# Cosmic_Pi_Analogue_V2_5_OHL_no_logo.net
KiCad netlist of a schematic drawn in EAGLE
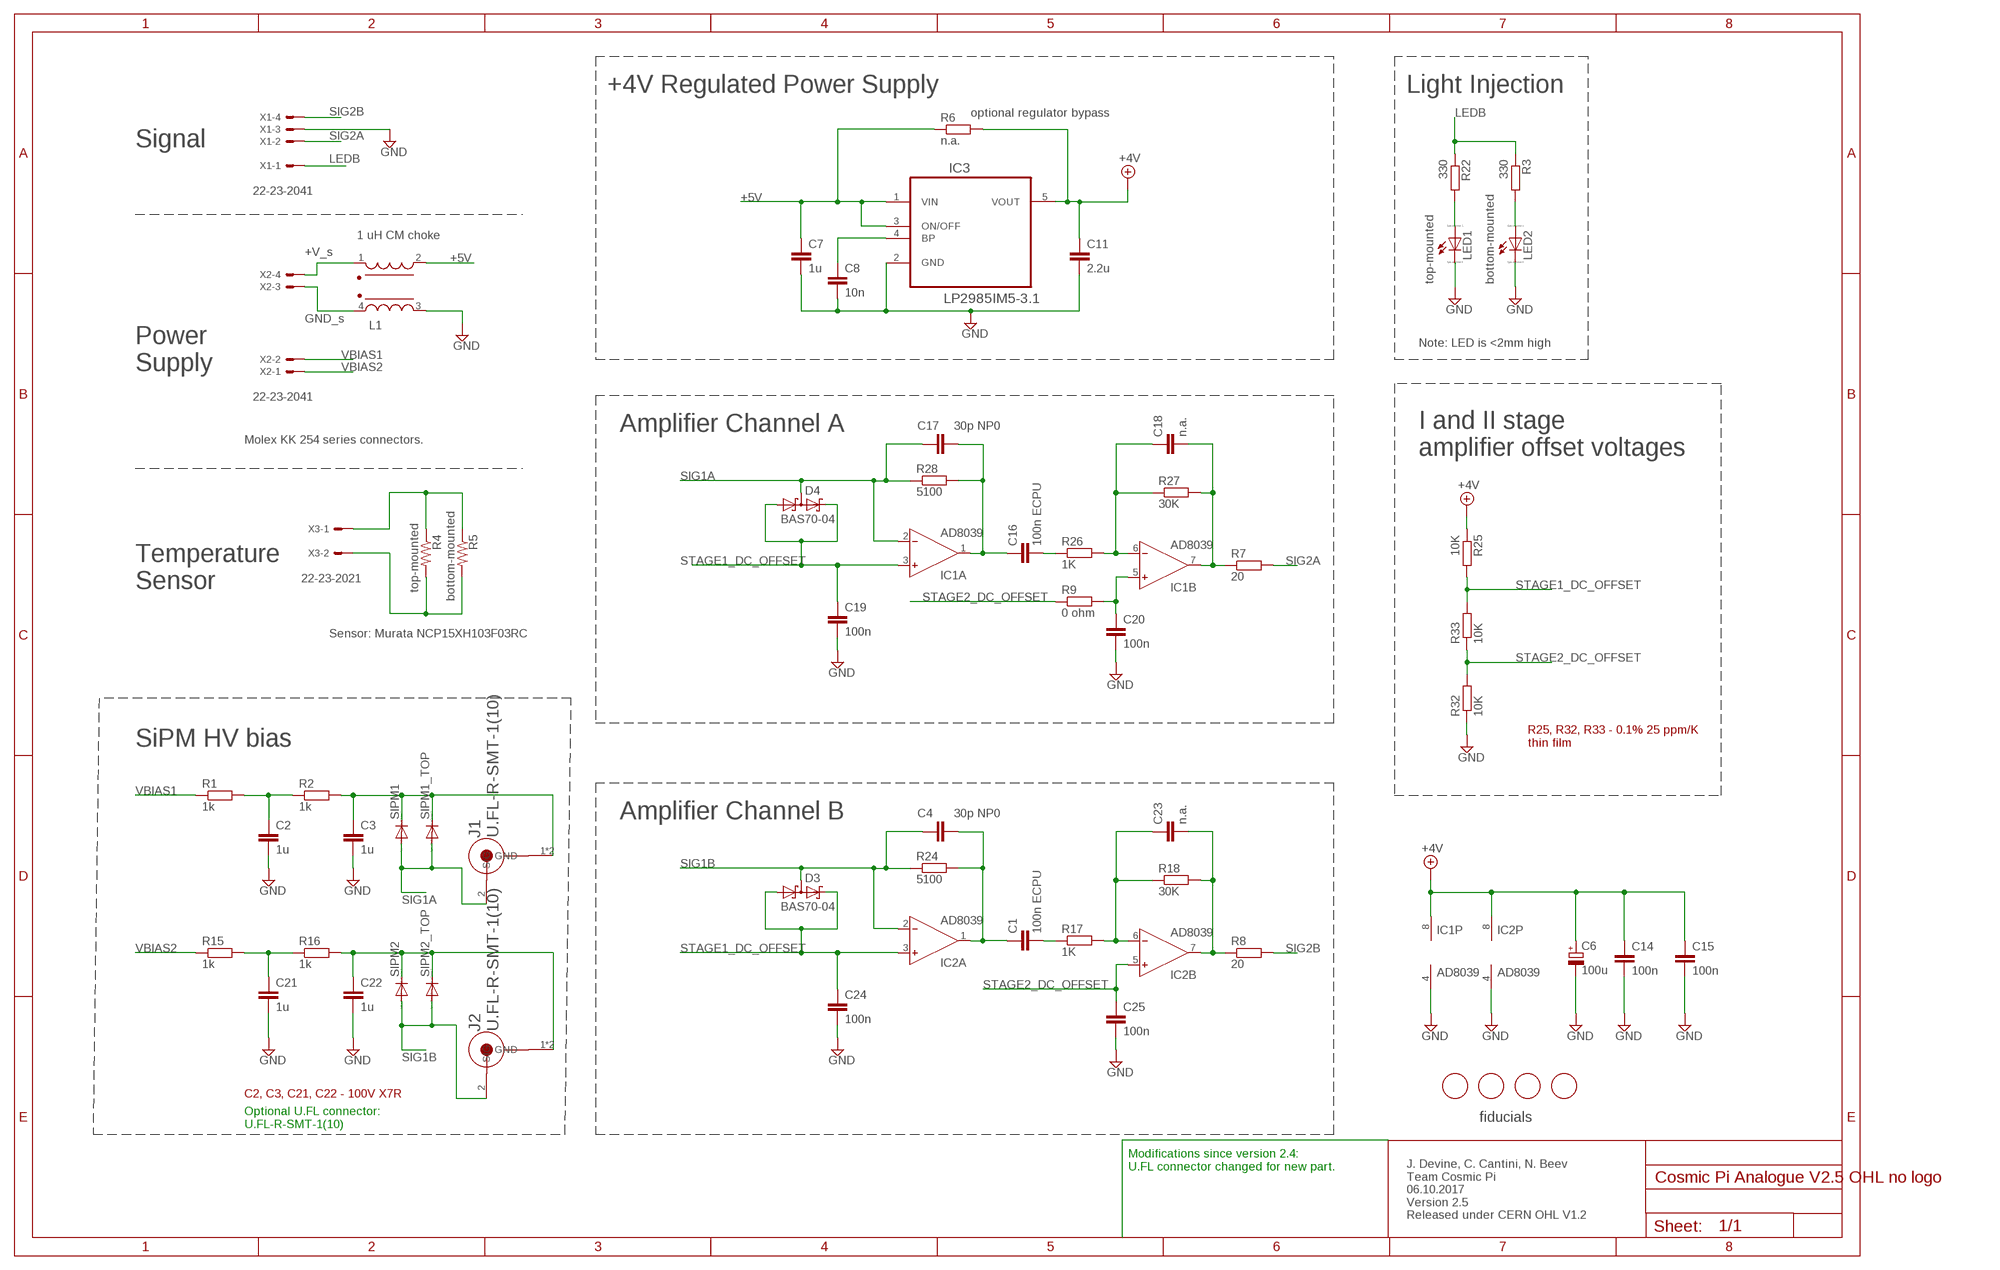
[diagram p0: schematic, sheet 1]

(export (version "E")
  (design (tool "Eeschema 10.0.6"))
  (components
    (comp (ref "C1")
      (value "100n ECPU")
      (footprint "eagle-import:C0805")
      (libsource (lib "eagle-import") (part "C-EUC0805"))
    )
    (comp (ref "C2")
      (value "1u")
      (footprint "eagle-import:C1206")
      (libsource (lib "eagle-import") (part "C-EUC1206"))
    )
    (comp (ref "C3")
      (value "1u")
      (footprint "eagle-import:C1206")
      (libsource (lib "eagle-import") (part "C-EUC1206"))
    )
    (comp (ref "C4")
      (value "30p NP0")
      (footprint "eagle-import:C0603")
      (libsource (lib "eagle-import") (part "C-EUC0603"))
    )
    (comp (ref "C6")
      (value "100u")
      (footprint "eagle-import:C_6032-28R")
      (libsource (lib "eagle-import") (part "CPOL-EUC/6032-28R"))
    )
    (comp (ref "C7")
      (value "1u")
      (footprint "eagle-import:C0603")
      (libsource (lib "eagle-import") (part "resistor_C-EUC0603"))
    )
    (comp (ref "C8")
      (value "10n")
      (footprint "eagle-import:C0603")
      (libsource (lib "eagle-import") (part "resistor_C-EUC0603"))
    )
    (comp (ref "C11")
      (value "2.2u")
      (footprint "eagle-import:C0603")
      (libsource (lib "eagle-import") (part "resistor_C-EUC0603"))
    )
    (comp (ref "C14")
      (value "100n")
      (footprint "eagle-import:C0603")
      (libsource (lib "eagle-import") (part "resistor_C-EUC0603"))
    )
    (comp (ref "C15")
      (value "100n")
      (footprint "eagle-import:C0603")
      (libsource (lib "eagle-import") (part "resistor_C-EUC0603"))
    )
    (comp (ref "C16")
      (value "100n ECPU")
      (footprint "eagle-import:C0805")
      (libsource (lib "eagle-import") (part "C-EUC0805"))
    )
    (comp (ref "C17")
      (value "30p NP0")
      (footprint "eagle-import:C0603")
      (libsource (lib "eagle-import") (part "C-EUC0603"))
    )
    (comp (ref "C18")
      (value "n.a.")
      (footprint "eagle-import:C0603")
      (libsource (lib "eagle-import") (part "C-EUC0603"))
    )
    (comp (ref "C19")
      (value "100n")
      (footprint "eagle-import:C0603")
      (libsource (lib "eagle-import") (part "resistor_C-EUC0603"))
    )
    (comp (ref "C20")
      (value "100n")
      (footprint "eagle-import:C0603")
      (libsource (lib "eagle-import") (part "resistor_C-EUC0603"))
    )
    (comp (ref "C21")
      (value "1u")
      (footprint "eagle-import:C1206")
      (libsource (lib "eagle-import") (part "C-EUC1206"))
    )
    (comp (ref "C22")
      (value "1u")
      (footprint "eagle-import:C1206")
      (libsource (lib "eagle-import") (part "C-EUC1206"))
    )
    (comp (ref "C23")
      (value "n.a.")
      (footprint "eagle-import:C0603")
      (libsource (lib "eagle-import") (part "C-EUC0603"))
    )
    (comp (ref "C24")
      (value "100n")
      (footprint "eagle-import:C0603")
      (libsource (lib "eagle-import") (part "resistor_C-EUC0603"))
    )
    (comp (ref "C25")
      (value "100n")
      (footprint "eagle-import:C0603")
      (libsource (lib "eagle-import") (part "resistor_C-EUC0603"))
    )
    (comp (ref "D3")
      (value "BAS70-04")
      (footprint "eagle-import:SOT23")
      (libsource (lib "eagle-import") (part "BAS70-04"))
    )
    (comp (ref "D4")
      (value "BAS70-04")
      (footprint "eagle-import:SOT23")
      (libsource (lib "eagle-import") (part "BAS70-04"))
    )
    (comp (ref "IC1")
      (value "AD8039")
      (footprint "eagle-import:SO8")
      (fields (field (name "MF") "ALTERA CORPORATION") (field (name "MPN") "AD8033ARZ"))
      (libsource (lib "eagle-import") (part "AD8033R"))
    )
    (comp (ref "IC2")
      (value "AD8039")
      (footprint "eagle-import:SO8")
      (fields (field (name "MF") "ALTERA CORPORATION") (field (name "MPN") "AD8033ARZ"))
      (libsource (lib "eagle-import") (part "AD8033R"))
    )
    (comp (ref "IC3")
      (value "LP2985IM5-3.1")
      (footprint "eagle-import:SOT95P284X120-5N")
      (libsource (lib "eagle-import") (part "LP2985IM5-3.1"))
    )
    (comp (ref "J1")
      (value "U.FL-R-SMT-1(10)")
      (footprint "eagle-import:HRS_U.FL-R-SMT-1(10)")
      (fields (field (name "MF") "Hirose"))
      (libsource (lib "eagle-import") (part "U.FL-R-SMT-1(10)"))
    )
    (comp (ref "J2")
      (value "U.FL-R-SMT-1(10)")
      (footprint "eagle-import:HRS_U.FL-R-SMT-1(10)")
      (fields (field (name "MF") "Hirose"))
      (libsource (lib "eagle-import") (part "U.FL-R-SMT-1(10)"))
    )
    (comp (ref "L1")
      (value "1 uH CM choke")
      (footprint "eagle-import:WE-CNSW_1812")
      (libsource (lib "eagle-import") (part "WE-CNSW_1812_744235601"))
    )
    (comp (ref "LED1")
      (value "top-mounted")
      (footprint "eagle-import:LED_SML0603")
      (libsource (lib "eagle-import") (part "LED_ESML0603"))
    )
    (comp (ref "LED2")
      (value "bottom-mounted")
      (footprint "eagle-import:LED_SML0603")
      (libsource (lib "eagle-import") (part "LED_ESML0603"))
    )
    (comp (ref "R1")
      (value "1k")
      (footprint "eagle-import:R1206")
      (libsource (lib "eagle-import") (part "R-EU_R1206"))
    )
    (comp (ref "R2")
      (value "1k")
      (footprint "eagle-import:R1206")
      (libsource (lib "eagle-import") (part "R-EU_R1206"))
    )
    (comp (ref "R3")
      (value "330")
      (footprint "eagle-import:R0603")
      (libsource (lib "eagle-import") (part "resistor_R-EU_R0603"))
    )
    (comp (ref "R4")
      (value "top-mounted")
      (footprint "eagle-import:R0402")
      (libsource (lib "eagle-import") (part "R-US_R0402"))
    )
    (comp (ref "R5")
      (value "bottom-mounted")
      (footprint "eagle-import:R0402")
      (libsource (lib "eagle-import") (part "R-US_R0402"))
    )
    (comp (ref "R6")
      (value "n.a.")
      (footprint "eagle-import:R0603")
      (libsource (lib "eagle-import") (part "R-EU_R0603"))
    )
    (comp (ref "R7")
      (value "20")
      (footprint "eagle-import:R0603")
      (libsource (lib "eagle-import") (part "R-EU_R0603"))
    )
    (comp (ref "R8")
      (value "20")
      (footprint "eagle-import:R0603")
      (libsource (lib "eagle-import") (part "R-EU_R0603"))
    )
    (comp (ref "R9")
      (value "0 ohm")
      (footprint "eagle-import:R1206")
      (libsource (lib "eagle-import") (part "R-EU_R1206"))
    )
    (comp (ref "R15")
      (value "1k")
      (footprint "eagle-import:R1206")
      (libsource (lib "eagle-import") (part "R-EU_R1206"))
    )
    (comp (ref "R16")
      (value "1k")
      (footprint "eagle-import:R1206")
      (libsource (lib "eagle-import") (part "R-EU_R1206"))
    )
    (comp (ref "R17")
      (value "1K")
      (footprint "eagle-import:R0603")
      (libsource (lib "eagle-import") (part "R-EU_R0603"))
    )
    (comp (ref "R18")
      (value "30K")
      (footprint "eagle-import:R0603")
      (libsource (lib "eagle-import") (part "R-EU_R0603"))
    )
    (comp (ref "R22")
      (value "330")
      (footprint "eagle-import:R0603")
      (libsource (lib "eagle-import") (part "resistor_R-EU_R0603"))
    )
    (comp (ref "R24")
      (value "5100")
      (footprint "eagle-import:R0603")
      (libsource (lib "eagle-import") (part "R-EU_R0603"))
    )
    (comp (ref "R25")
      (value "10K")
      (footprint "eagle-import:R0805")
      (libsource (lib "eagle-import") (part "R-EU_R0805"))
    )
    (comp (ref "R26")
      (value "1K")
      (footprint "eagle-import:R0603")
      (libsource (lib "eagle-import") (part "R-EU_R0603"))
    )
    (comp (ref "R27")
      (value "30K")
      (footprint "eagle-import:R0603")
      (libsource (lib "eagle-import") (part "R-EU_R0603"))
    )
    (comp (ref "R28")
      (value "5100")
      (footprint "eagle-import:R0603")
      (libsource (lib "eagle-import") (part "R-EU_R0603"))
    )
    (comp (ref "R32")
      (value "10K")
      (footprint "eagle-import:R0805")
      (libsource (lib "eagle-import") (part "R-EU_R0805"))
    )
    (comp (ref "R33")
      (value "10K")
      (footprint "eagle-import:R0805")
      (libsource (lib "eagle-import") (part "R-EU_R0805"))
    )
    (comp (ref "SIPM1")
      (value "DIODE-ADVANSID")
      (footprint "eagle-import:ASD-NUV3S-P")
      (libsource (lib "eagle-import") (part "DIODE-ADVANSID"))
    )
    (comp (ref "SIPM1_TOP")
      (value "DIODE-ADVANSID")
      (footprint "eagle-import:ASD-NUV3S-P")
      (libsource (lib "eagle-import") (part "DIODE-ADVANSID"))
    )
    (comp (ref "SIPM2")
      (value "DIODE-ADVANSID")
      (footprint "eagle-import:ASD-NUV3S-P")
      (libsource (lib "eagle-import") (part "DIODE-ADVANSID"))
    )
    (comp (ref "SIPM2_TOP")
      (value "DIODE-ADVANSID")
      (footprint "eagle-import:ASD-NUV3S-P")
      (libsource (lib "eagle-import") (part "DIODE-ADVANSID"))
    )
    (comp (ref "U$2")
      (value "FIDUCIAL")
      (footprint "eagle-import:FIDUCIAL_1MM")
      (libsource (lib "eagle-import") (part "FIDUCIAL"))
    )
    (comp (ref "U$3")
      (value "FIDUCIAL")
      (footprint "eagle-import:FIDUCIAL_1MM")
      (libsource (lib "eagle-import") (part "FIDUCIAL"))
    )
    (comp (ref "U$4")
      (value "FIDUCIAL")
      (footprint "eagle-import:FIDUCIAL_1MM")
      (libsource (lib "eagle-import") (part "FIDUCIAL"))
    )
    (comp (ref "U$5")
      (value "FIDUCIAL")
      (footprint "eagle-import:FIDUCIAL_1MM")
      (libsource (lib "eagle-import") (part "FIDUCIAL"))
    )
    (comp (ref "X1")
      (value "22-23-2041")
      (footprint "eagle-import:22-23-2041")
      (fields (field (name "MF") "MOLEX"))
      (libsource (lib "eagle-import") (part "22-23-2041"))
    )
    (comp (ref "X2")
      (value "22-23-2041")
      (footprint "eagle-import:22-23-2041")
      (fields (field (name "MF") "MOLEX"))
      (libsource (lib "eagle-import") (part "22-23-2041"))
    )
    (comp (ref "X3")
      (value "22-23-2021")
      (footprint "eagle-import:22-23-2021")
      (fields (field (name "MF") "MOLEX"))
      (libsource (lib "eagle-import") (part "22-23-2021"))
    )
  )
  (nets
    (net (code "1") (name "+4V") (class "Default")
      (node (ref "C11") (pin "1") (pinfunction "1_1") (pintype "passive"))
      (node (ref "C14") (pin "1") (pinfunction "1_1") (pintype "passive"))
      (node (ref "C15") (pin "1") (pinfunction "1_1") (pintype "passive"))
      (node (ref "C6") (pin "+") (pinfunction "+_+") (pintype "passive"))
      (node (ref "IC1") (pin "8") (pinfunction "V+_8") (pintype "power_in"))
      (node (ref "IC2") (pin "8") (pinfunction "V+_8") (pintype "power_in"))
      (node (ref "IC3") (pin "5") (pinfunction "VOUT_5") (pintype "output"))
      (node (ref "R25") (pin "1") (pinfunction "1_1") (pintype "passive"))
      (node (ref "R6") (pin "2") (pinfunction "2_2") (pintype "passive"))
    )
    (net (code "2") (name "/+5V") (class "Default")
      (node (ref "C7") (pin "1") (pinfunction "1_1") (pintype "passive"))
      (node (ref "IC3") (pin "1") (pinfunction "VIN_1") (pintype "power_in"))
      (node (ref "IC3") (pin "3") (pinfunction "ON/OFF_3") (pintype "input"))
      (node (ref "L1") (pin "2") (pinfunction "3_2") (pintype "passive"))
      (node (ref "R6") (pin "1") (pinfunction "1_1") (pintype "passive"))
    )
    (net (code "3") (name "/LEDB") (class "Default")
      (node (ref "R22") (pin "1") (pinfunction "1_1") (pintype "passive"))
      (node (ref "R3") (pin "1") (pinfunction "1_1") (pintype "passive"))
      (node (ref "X1") (pin "1") (pinfunction "S_1") (pintype "passive"))
    )
    (net (code "4") (name "/SIG1A") (class "Default")
      (node (ref "C17") (pin "1") (pinfunction "1_1") (pintype "passive"))
      (node (ref "D4") (pin "3") (pinfunction "C1A2_3") (pintype "passive"))
      (node (ref "IC1") (pin "2") (pinfunction "IN-_2") (pintype "input"))
      (node (ref "J1") (pin "2") (pinfunction "SIG_2") (pintype "passive"))
      (node (ref "R28") (pin "1") (pinfunction "1_1") (pintype "passive"))
      (node (ref "SIPM1") (pin "P$2") (pinfunction "A_P$2") (pintype "passive"))
      (node (ref "SIPM1_TOP") (pin "P$2") (pinfunction "A_P$2") (pintype "passive"))
    )
    (net (code "5") (name "/SIG1B") (class "Default")
      (node (ref "C4") (pin "1") (pinfunction "1_1") (pintype "passive"))
      (node (ref "D3") (pin "3") (pinfunction "C1A2_3") (pintype "passive"))
      (node (ref "IC2") (pin "2") (pinfunction "IN-_2") (pintype "input"))
      (node (ref "J2") (pin "2") (pinfunction "SIG_2") (pintype "passive"))
      (node (ref "R24") (pin "1") (pinfunction "1_1") (pintype "passive"))
      (node (ref "SIPM2") (pin "P$2") (pinfunction "A_P$2") (pintype "passive"))
      (node (ref "SIPM2_TOP") (pin "P$2") (pinfunction "A_P$2") (pintype "passive"))
    )
    (net (code "6") (name "/SIG2A") (class "Default")
      (node (ref "R7") (pin "2") (pinfunction "2_2") (pintype "passive"))
      (node (ref "X1") (pin "2") (pinfunction "S_2") (pintype "passive"))
    )
    (net (code "7") (name "/SIG2B") (class "Default")
      (node (ref "R8") (pin "2") (pinfunction "2_2") (pintype "passive"))
      (node (ref "X1") (pin "4") (pinfunction "S_4") (pintype "passive"))
    )
    (net (code "8") (name "/STAGE1_DC_OFFSET") (class "Default")
      (node (ref "C19") (pin "1") (pinfunction "1_1") (pintype "passive"))
      (node (ref "C24") (pin "1") (pinfunction "1_1") (pintype "passive"))
      (node (ref "D3") (pin "1") (pinfunction "A1_1") (pintype "passive"))
      (node (ref "D3") (pin "2") (pinfunction "C2_2") (pintype "passive"))
      (node (ref "D4") (pin "1") (pinfunction "A1_1") (pintype "passive"))
      (node (ref "D4") (pin "2") (pinfunction "C2_2") (pintype "passive"))
      (node (ref "IC1") (pin "3") (pinfunction "IN+_3") (pintype "input"))
      (node (ref "IC2") (pin "3") (pinfunction "IN+_3") (pintype "input"))
      (node (ref "R25") (pin "2") (pinfunction "2_2") (pintype "passive"))
      (node (ref "R33") (pin "2") (pinfunction "2_2") (pintype "passive"))
    )
    (net (code "9") (name "/STAGE2_DC_OFFSET") (class "Default")
      (node (ref "C25") (pin "1") (pinfunction "1_1") (pintype "passive"))
      (node (ref "IC2") (pin "5") (pinfunction "IN+_5") (pintype "input"))
      (node (ref "R32") (pin "2") (pinfunction "2_2") (pintype "passive"))
      (node (ref "R33") (pin "1") (pinfunction "1_1") (pintype "passive"))
      (node (ref "R9") (pin "1") (pinfunction "1_1") (pintype "passive"))
    )
    (net (code "10") (name "/VBIAS1") (class "Default")
      (node (ref "R1") (pin "1") (pinfunction "1_1") (pintype "passive"))
      (node (ref "X2") (pin "2") (pinfunction "S_2") (pintype "passive"))
    )
    (net (code "11") (name "/VBIAS2") (class "Default")
      (node (ref "R15") (pin "1") (pinfunction "1_1") (pintype "passive"))
      (node (ref "X2") (pin "1") (pinfunction "S_1") (pintype "passive"))
    )
    (net (code "12") (name "GND") (class "Default")
      (node (ref "C11") (pin "2") (pinfunction "2_2") (pintype "passive"))
      (node (ref "C14") (pin "2") (pinfunction "2_2") (pintype "passive"))
      (node (ref "C15") (pin "2") (pinfunction "2_2") (pintype "passive"))
      (node (ref "C19") (pin "2") (pinfunction "2_2") (pintype "passive"))
      (node (ref "C2") (pin "2") (pinfunction "2_2") (pintype "passive"))
      (node (ref "C20") (pin "2") (pinfunction "2_2") (pintype "passive"))
      (node (ref "C21") (pin "2") (pinfunction "2_2") (pintype "passive"))
      (node (ref "C22") (pin "2") (pinfunction "2_2") (pintype "passive"))
      (node (ref "C24") (pin "2") (pinfunction "2_2") (pintype "passive"))
      (node (ref "C25") (pin "2") (pinfunction "2_2") (pintype "passive"))
      (node (ref "C3") (pin "2") (pinfunction "2_2") (pintype "passive"))
      (node (ref "C6") (pin "-") (pinfunction "-_-") (pintype "passive"))
      (node (ref "C7") (pin "2") (pinfunction "2_2") (pintype "passive"))
      (node (ref "C8") (pin "2") (pinfunction "2_2") (pintype "passive"))
      (node (ref "IC1") (pin "4") (pinfunction "V-_4") (pintype "power_in"))
      (node (ref "IC2") (pin "4") (pinfunction "V-_4") (pintype "power_in"))
      (node (ref "IC3") (pin "2") (pinfunction "GND_2") (pintype "passive"))
      (node (ref "L1") (pin "3") (pinfunction "2_3") (pintype "passive"))
      (node (ref "LED1") (pin "C") (pinfunction "C_C") (pintype "passive"))
      (node (ref "LED2") (pin "C") (pinfunction "C_C") (pintype "passive"))
      (node (ref "R32") (pin "1") (pinfunction "1_1") (pintype "passive"))
      (node (ref "X1") (pin "3") (pinfunction "S_3") (pintype "passive"))
    )
    (net (code "13") (name "Net-(C1-Pad2)") (class "Default")
      (node (ref "C1") (pin "2") (pinfunction "2_2") (pintype "passive"))
      (node (ref "R17") (pin "1") (pinfunction "1_1") (pintype "passive"))
    )
    (net (code "14") (name "Net-(C2-Pad1)") (class "Default")
      (node (ref "C2") (pin "1") (pinfunction "1_1") (pintype "passive"))
      (node (ref "R1") (pin "2") (pinfunction "2_2") (pintype "passive"))
      (node (ref "R2") (pin "1") (pinfunction "1_1") (pintype "passive"))
    )
    (net (code "15") (name "Net-(C16-Pad2)") (class "Default")
      (node (ref "C16") (pin "2") (pinfunction "2_2") (pintype "passive"))
      (node (ref "R26") (pin "1") (pinfunction "1_1") (pintype "passive"))
    )
    (net (code "16") (name "Net-(C21-Pad1)") (class "Default")
      (node (ref "C21") (pin "1") (pinfunction "1_1") (pintype "passive"))
      (node (ref "R15") (pin "2") (pinfunction "2_2") (pintype "passive"))
      (node (ref "R16") (pin "1") (pinfunction "1_1") (pintype "passive"))
    )
    (net (code "17") (name "Net-(IC1A-OUT)") (class "Default")
      (node (ref "C16") (pin "1") (pinfunction "1_1") (pintype "passive"))
      (node (ref "C17") (pin "2") (pinfunction "2_2") (pintype "passive"))
      (node (ref "IC1") (pin "1") (pinfunction "OUT_1") (pintype "output"))
      (node (ref "R28") (pin "2") (pinfunction "2_2") (pintype "passive"))
    )
    (net (code "18") (name "Net-(IC1B-IN+)") (class "Default")
      (node (ref "C20") (pin "1") (pinfunction "1_1") (pintype "passive"))
      (node (ref "IC1") (pin "5") (pinfunction "IN+_5") (pintype "input"))
      (node (ref "R9") (pin "2") (pinfunction "2_2") (pintype "passive"))
    )
    (net (code "19") (name "Net-(IC1B-IN-)") (class "Default")
      (node (ref "C18") (pin "1") (pinfunction "1_1") (pintype "passive"))
      (node (ref "IC1") (pin "6") (pinfunction "IN-_6") (pintype "input"))
      (node (ref "R26") (pin "2") (pinfunction "2_2") (pintype "passive"))
      (node (ref "R27") (pin "1") (pinfunction "1_1") (pintype "passive"))
    )
    (net (code "20") (name "Net-(IC1B-OUT)") (class "Default")
      (node (ref "C18") (pin "2") (pinfunction "2_2") (pintype "passive"))
      (node (ref "IC1") (pin "7") (pinfunction "OUT_7") (pintype "output"))
      (node (ref "R27") (pin "2") (pinfunction "2_2") (pintype "passive"))
      (node (ref "R7") (pin "1") (pinfunction "1_1") (pintype "passive"))
    )
    (net (code "21") (name "Net-(IC2A-OUT)") (class "Default")
      (node (ref "C1") (pin "1") (pinfunction "1_1") (pintype "passive"))
      (node (ref "C4") (pin "2") (pinfunction "2_2") (pintype "passive"))
      (node (ref "IC2") (pin "1") (pinfunction "OUT_1") (pintype "output"))
      (node (ref "R24") (pin "2") (pinfunction "2_2") (pintype "passive"))
    )
    (net (code "22") (name "Net-(IC2B-IN-)") (class "Default")
      (node (ref "C23") (pin "1") (pinfunction "1_1") (pintype "passive"))
      (node (ref "IC2") (pin "6") (pinfunction "IN-_6") (pintype "input"))
      (node (ref "R17") (pin "2") (pinfunction "2_2") (pintype "passive"))
      (node (ref "R18") (pin "1") (pinfunction "1_1") (pintype "passive"))
    )
    (net (code "23") (name "Net-(IC2B-OUT)") (class "Default")
      (node (ref "C23") (pin "2") (pinfunction "2_2") (pintype "passive"))
      (node (ref "IC2") (pin "7") (pinfunction "OUT_7") (pintype "output"))
      (node (ref "R18") (pin "2") (pinfunction "2_2") (pintype "passive"))
      (node (ref "R8") (pin "1") (pinfunction "1_1") (pintype "passive"))
    )
    (net (code "24") (name "Net-(IC3-BP)") (class "Default")
      (node (ref "C8") (pin "1") (pinfunction "1_1") (pintype "passive"))
      (node (ref "IC3") (pin "4") (pinfunction "BP_4") (pintype "input"))
    )
    (net (code "25") (name "Net-(L1-1)") (class "Default")
      (node (ref "L1") (pin "4") (pinfunction "1_4") (pintype "passive"))
      (node (ref "X2") (pin "3") (pinfunction "S_3") (pintype "passive"))
    )
    (net (code "26") (name "Net-(L1-4)") (class "Default")
      (node (ref "L1") (pin "1") (pinfunction "4_1") (pintype "passive"))
      (node (ref "X2") (pin "4") (pinfunction "S_4") (pintype "passive"))
    )
    (net (code "27") (name "Net-(LED1-PadA)") (class "Default")
      (node (ref "LED1") (pin "A") (pinfunction "A_A") (pintype "passive"))
      (node (ref "R22") (pin "2") (pinfunction "2_2") (pintype "passive"))
    )
    (net (code "28") (name "Net-(LED2-PadA)") (class "Default")
      (node (ref "LED2") (pin "A") (pinfunction "A_A") (pintype "passive"))
      (node (ref "R3") (pin "2") (pinfunction "2_2") (pintype "passive"))
    )
    (net (code "29") (name "Net-(SIPM1-C)") (class "Default")
      (node (ref "C3") (pin "1") (pinfunction "1_1") (pintype "passive"))
      (node (ref "J1") (pin "1") (pinfunction "GND_1") (pintype "passive"))
      (node (ref "J1") (pin "3") (pinfunction "GND_3") (pintype "passive"))
      (node (ref "R2") (pin "2") (pinfunction "2_2") (pintype "passive"))
      (node (ref "SIPM1") (pin "P$1") (pinfunction "C_P$1") (pintype "passive"))
      (node (ref "SIPM1_TOP") (pin "P$1") (pinfunction "C_P$1") (pintype "passive"))
    )
    (net (code "30") (name "Net-(SIPM2-C)") (class "Default")
      (node (ref "C22") (pin "1") (pinfunction "1_1") (pintype "passive"))
      (node (ref "J2") (pin "1") (pinfunction "GND_1") (pintype "passive"))
      (node (ref "J2") (pin "3") (pinfunction "GND_3") (pintype "passive"))
      (node (ref "R16") (pin "2") (pinfunction "2_2") (pintype "passive"))
      (node (ref "SIPM2") (pin "P$1") (pinfunction "C_P$1") (pintype "passive"))
      (node (ref "SIPM2_TOP") (pin "P$1") (pinfunction "C_P$1") (pintype "passive"))
    )
    (net (code "31") (name "Net-(X3A-S)") (class "Default")
      (node (ref "R4") (pin "1") (pinfunction "1_1") (pintype "passive"))
      (node (ref "R5") (pin "1") (pinfunction "1_1") (pintype "passive"))
      (node (ref "X3") (pin "1") (pinfunction "S_1") (pintype "passive"))
    )
    (net (code "32") (name "Net-(X3B-S)") (class "Default")
      (node (ref "R4") (pin "2") (pinfunction "2_2") (pintype "passive"))
      (node (ref "R5") (pin "2") (pinfunction "2_2") (pintype "passive"))
      (node (ref "X3") (pin "2") (pinfunction "S_2") (pintype "passive"))
    )
  )
)
